# LIA.net
KiCad netlist of a schematic drawn in Altium Designer
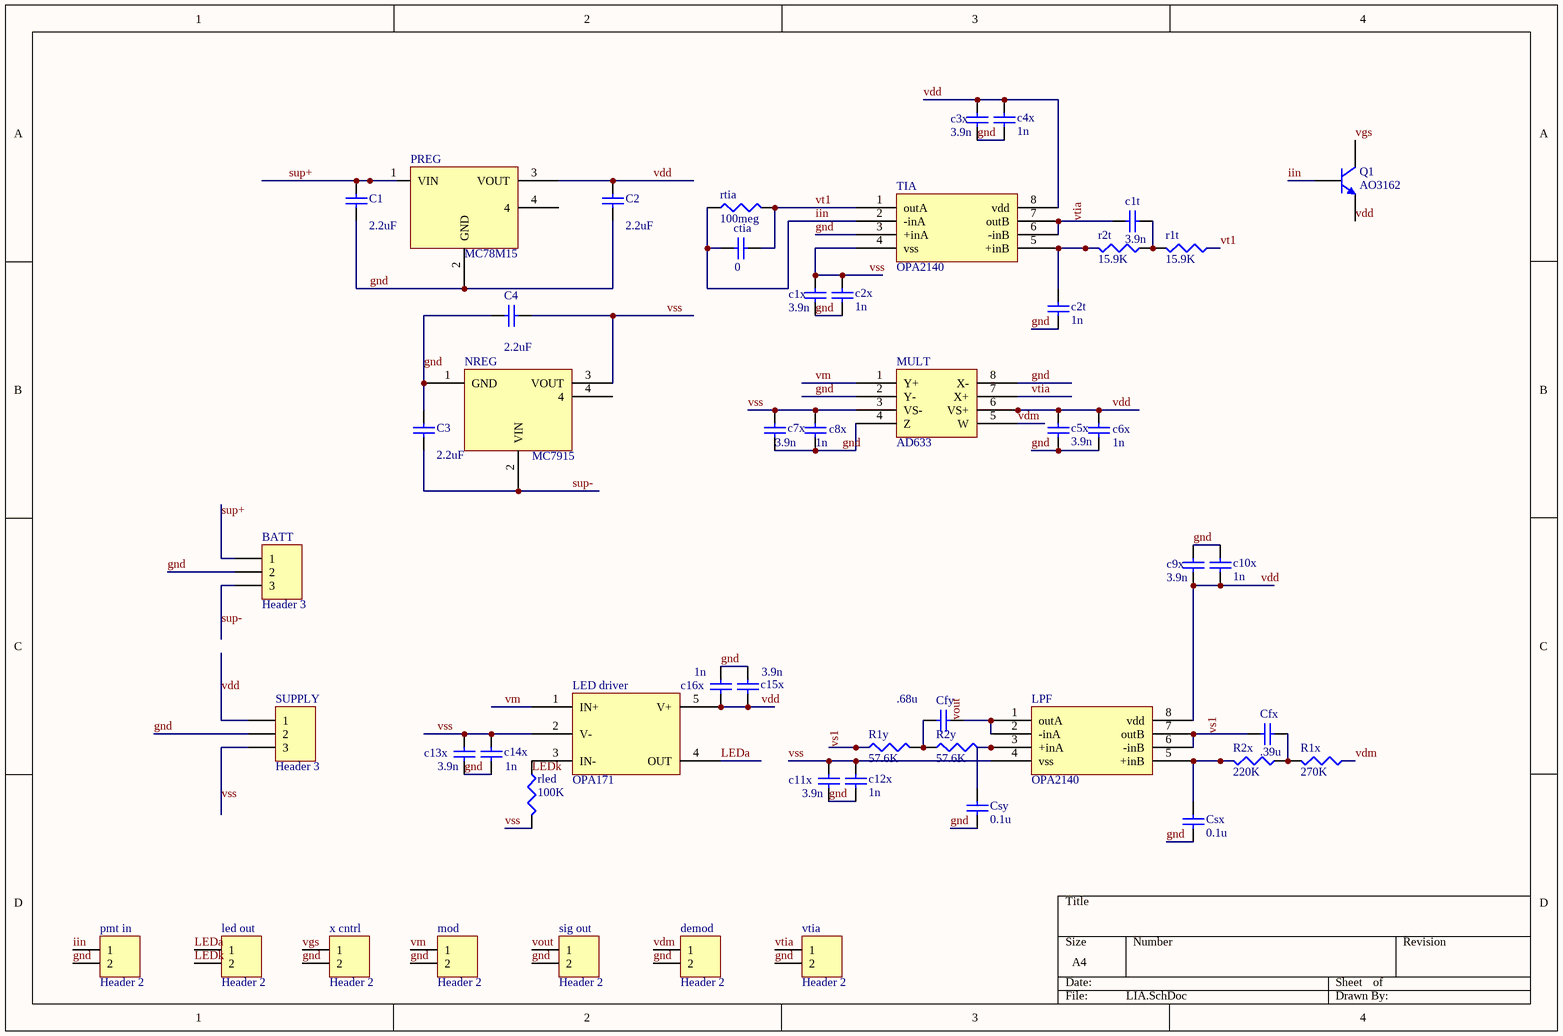
[diagram p0: LIA.SchDoc]

(export (version "E")
  (design (tool "Eeschema 10.0.6"))
  (components
    (comp (ref "BATT")
      (value "Header 3")
      (footprint "HDR1X3")
      (description "Header, 3-Pin")
      (fields (field (name "PUBLISHER") "Altium Limited"))
      (libsource (lib "Miscellaneous Connectors") (part "Header 3"))
    )
    (comp (ref "C1")
      (value "2.2uF")
      (footprint "0402")
      (description "Ceramic Chip Capacitor - Standard")
      (fields (field (name "Comment") "GRM155R61C225KE11D") (field (name "PUBLISHER") "Altium Limited"))
      (libsource (lib "KEMET Chip Capacitor") (part "C0402"))
    )
    (comp (ref "c1t")
      (value "3.9n")
      (footprint "0402")
      (description "Ceramic Chip Capacitor - Standard")
      (fields (field (name "Comment") "GRM155R71H392KA01D") (field (name "PUBLISHER") "Altium Limited"))
      (libsource (lib "KEMET Chip Capacitor") (part "C0402"))
    )
    (comp (ref "c1x")
      (value "3.9n")
      (footprint "0402")
      (description "Ceramic Chip Capacitor - Standard")
      (fields (field (name "Comment") "GRM155R71H392KA01D") (field (name "PUBLISHER") "Altium Limited"))
      (libsource (lib "KEMET Chip Capacitor") (part "C0402"))
    )
    (comp (ref "C2")
      (value "2.2uF")
      (footprint "0402")
      (description "Ceramic Chip Capacitor - Standard")
      (fields (field (name "Comment") "GRM155R61C225KE11D") (field (name "PUBLISHER") "Altium Limited"))
      (libsource (lib "KEMET Chip Capacitor") (part "C0402"))
    )
    (comp (ref "c2t")
      (value "1n")
      (footprint "0402")
      (description "Ceramic Chip Capacitor - Standard")
      (fields (field (name "Comment") "GRM155R71H102KA01D") (field (name "PUBLISHER") "Altium Limited"))
      (libsource (lib "KEMET Chip Capacitor") (part "C0402"))
    )
    (comp (ref "c2x")
      (value "1n")
      (footprint "0402")
      (description "Ceramic Chip Capacitor - Standard")
      (fields (field (name "Comment") "GRM155R71H102KA01D") (field (name "PUBLISHER") "Altium Limited"))
      (libsource (lib "KEMET Chip Capacitor") (part "C0402"))
    )
    (comp (ref "C3")
      (value "2.2uF")
      (footprint "0402")
      (description "Ceramic Chip Capacitor - Standard")
      (fields (field (name "Comment") "GRM155R61C225KE11D") (field (name "PUBLISHER") "Altium Limited"))
      (libsource (lib "KEMET Chip Capacitor") (part "C0402"))
    )
    (comp (ref "c3x")
      (value "3.9n")
      (footprint "0402")
      (description "Ceramic Chip Capacitor - Standard")
      (fields (field (name "Comment") "GRM155R71H392KA01D") (field (name "PUBLISHER") "Altium Limited"))
      (libsource (lib "KEMET Chip Capacitor") (part "C0402"))
    )
    (comp (ref "C4")
      (value "2.2uF")
      (footprint "0402")
      (description "Ceramic Chip Capacitor - Standard")
      (fields (field (name "Comment") "GRM155R61C225KE11D") (field (name "PUBLISHER") "Altium Limited"))
      (libsource (lib "KEMET Chip Capacitor") (part "C0402"))
    )
    (comp (ref "c4x")
      (value "1n")
      (footprint "0402")
      (description "Ceramic Chip Capacitor - Standard")
      (fields (field (name "Comment") "GRM155R71H102KA01D") (field (name "PUBLISHER") "Altium Limited"))
      (libsource (lib "KEMET Chip Capacitor") (part "C0402"))
    )
    (comp (ref "c5x")
      (value "3.9n")
      (footprint "0402")
      (description "Ceramic Chip Capacitor - Standard")
      (fields (field (name "Comment") "GRM155R71H392KA01D") (field (name "PUBLISHER") "Altium Limited"))
      (libsource (lib "KEMET Chip Capacitor") (part "C0402"))
    )
    (comp (ref "c6x")
      (value "1n")
      (footprint "0402")
      (description "Ceramic Chip Capacitor - Standard")
      (fields (field (name "Comment") "GRM155R71H102KA01D") (field (name "PUBLISHER") "Altium Limited"))
      (libsource (lib "KEMET Chip Capacitor") (part "C0402"))
    )
    (comp (ref "c7x")
      (value "3.9n")
      (footprint "0402")
      (description "Ceramic Chip Capacitor - Standard")
      (fields (field (name "Comment") "GRM155R71H392KA01D") (field (name "PUBLISHER") "Altium Limited"))
      (libsource (lib "KEMET Chip Capacitor") (part "C0402"))
    )
    (comp (ref "c8x")
      (value "1n")
      (footprint "0402")
      (description "Ceramic Chip Capacitor - Standard")
      (fields (field (name "Comment") "GRM155R71H102KA01D") (field (name "PUBLISHER") "Altium Limited"))
      (libsource (lib "KEMET Chip Capacitor") (part "C0402"))
    )
    (comp (ref "c9x")
      (value "3.9n")
      (footprint "0402")
      (description "Ceramic Chip Capacitor - Standard")
      (fields (field (name "Comment") "GRM155R71H392KA01D") (field (name "PUBLISHER") "Altium Limited"))
      (libsource (lib "KEMET Chip Capacitor") (part "C0402"))
    )
    (comp (ref "c10x")
      (value "1n")
      (footprint "0402")
      (description "Ceramic Chip Capacitor - Standard")
      (fields (field (name "Comment") "GRM155R71H102KA01D") (field (name "PUBLISHER") "Altium Limited"))
      (libsource (lib "KEMET Chip Capacitor") (part "C0402"))
    )
    (comp (ref "c11x")
      (value "3.9n")
      (footprint "0402")
      (description "Ceramic Chip Capacitor - Standard")
      (fields (field (name "Comment") "GRM155R71H392KA01D") (field (name "PUBLISHER") "Altium Limited"))
      (libsource (lib "KEMET Chip Capacitor") (part "C0402"))
    )
    (comp (ref "c12x")
      (value "1n")
      (footprint "0402")
      (description "Ceramic Chip Capacitor - Standard")
      (fields (field (name "Comment") "GRM155R71H102KA01D") (field (name "PUBLISHER") "Altium Limited"))
      (libsource (lib "KEMET Chip Capacitor") (part "C0402"))
    )
    (comp (ref "c13x")
      (value "3.9n")
      (footprint "0402")
      (description "Ceramic Chip Capacitor - Standard")
      (fields (field (name "Comment") "GRM155R71H392KA01D") (field (name "PUBLISHER") "Altium Limited"))
      (libsource (lib "KEMET Chip Capacitor") (part "C0402"))
    )
    (comp (ref "c14x")
      (value "1n")
      (footprint "0402")
      (description "Ceramic Chip Capacitor - Standard")
      (fields (field (name "Comment") "GRM155R71H102KA01D") (field (name "PUBLISHER") "Altium Limited"))
      (libsource (lib "KEMET Chip Capacitor") (part "C0402"))
    )
    (comp (ref "c15x")
      (value "3.9n")
      (footprint "0402")
      (description "Ceramic Chip Capacitor - Standard")
      (fields (field (name "Comment") "GRM155R71H392KA01D") (field (name "PUBLISHER") "Altium Limited"))
      (libsource (lib "KEMET Chip Capacitor") (part "C0402"))
    )
    (comp (ref "c16x")
      (value "1n")
      (footprint "0402")
      (description "Ceramic Chip Capacitor - Standard")
      (fields (field (name "Comment") "GRM155R71H102KA01D") (field (name "PUBLISHER") "Altium Limited"))
      (libsource (lib "KEMET Chip Capacitor") (part "C0402"))
    )
    (comp (ref "Cfx")
      (value ".39u")
      (footprint "0402")
      (description "Ceramic Chip Capacitor - Standard")
      (fields (field (name "Comment") "GRM155R61A394KE15D") (field (name "PUBLISHER") "Altium Limited"))
      (libsource (lib "KEMET Chip Capacitor") (part "C0402"))
    )
    (comp (ref "Cfy")
      (value ".68u")
      (footprint "0402")
      (description "Ceramic Chip Capacitor - Standard")
      (fields (field (name "Comment") "C1005X5R1C684K050BC") (field (name "PUBLISHER") "Altium Limited"))
      (libsource (lib "KEMET Chip Capacitor") (part "C0402"))
    )
    (comp (ref "Csx")
      (value "0.1u")
      (footprint "0402")
      (description "Ceramic Chip Capacitor - Standard")
      (fields (field (name "Comment") "GRM155R61C104KA88J") (field (name "PUBLISHER") "Altium Limited"))
      (libsource (lib "KEMET Chip Capacitor") (part "C0402"))
    )
    (comp (ref "Csy")
      (value "0.1u")
      (footprint "0402")
      (description "Ceramic Chip Capacitor - Standard")
      (fields (field (name "Comment") "GRM155R61C104KA88J") (field (name "PUBLISHER") "Altium Limited"))
      (libsource (lib "KEMET Chip Capacitor") (part "C0402"))
    )
    (comp (ref "ctia")
      (value "0")
      (footprint "1206")
      (description "Ceramic Chip Capacitor - Standard")
      (fields (field (name "PUBLISHER") "Altium Limited"))
      (libsource (lib "KEMET Chip Capacitor") (part "C1210"))
    )
    (comp (ref "demod")
      (value "Header 2")
      (footprint "HDR1X2")
      (description "Header, 2-Pin")
      (fields (field (name "PUBLISHER") "Altium Limited"))
      (libsource (lib "Miscellaneous Connectors") (part "Header 2"))
    )
    (comp (ref "LED driver")
      (value "OPA171")
      (footprint "S5")
      (description "Single supply opamp SOT 553")
      (libsource (lib "katschematic") (part "OPA171"))
    )
    (comp (ref "led out")
      (value "Header 2")
      (footprint "HDR1X2")
      (description "Header, 2-Pin")
      (fields (field (name "PUBLISHER") "Altium Limited"))
      (libsource (lib "Miscellaneous Connectors") (part "Header 2"))
    )
    (comp (ref "LPF")
      (value "OPA2140")
      (description "dual channel JFET op amp")
      (libsource (lib "Schlib1") (part "OPA2211"))
    )
    (comp (ref "mod")
      (value "Header 2")
      (footprint "HDR1X2")
      (description "Header, 2-Pin")
      (fields (field (name "PUBLISHER") "Altium Limited"))
      (libsource (lib "Miscellaneous Connectors") (part "Header 2"))
    )
    (comp (ref "MULT")
      (value "AD633")
      (footprint "D008_L")
      (description "Analog multiplier")
      (libsource (lib "katschematic") (part "AD633"))
    )
    (comp (ref "NREG")
      (value "MC7915")
      (footprint "D2PAK_L")
      (description "-15 V LDO regulator")
      (libsource (lib "katschematic") (part "MC7915"))
    )
    (comp (ref "pmt in")
      (value "Header 2")
      (footprint "HDR1X2")
      (description "Header, 2-Pin")
      (fields (field (name "PUBLISHER") "Altium Limited"))
      (libsource (lib "Miscellaneous Connectors") (part "Header 2"))
    )
    (comp (ref "PREG")
      (value "MC78M15")
      (footprint "D2PAK_L")
      (description "+15 V LDO regulator")
      (libsource (lib "katschematic") (part "MC78M15"))
    )
    (comp (ref "Q1")
      (value "AO3162")
      (footprint "SOT-23B_N")
      (description "NPN Bipolar Transistor")
      (fields (field (name "PUBLISHER") "Altium Limited"))
      (libsource (lib "Miscellaneous Devices") (part "QNPN"))
    )
    (comp (ref "r1t")
      (value "15.9K")
      (footprint "J1-0603")
      (description "Resistor")
      (fields (field (name "Comment") "RC0603JR-0716KL") (field (name "PUBLISHER") "Altium Limited"))
      (libsource (lib "Miscellaneous Devices") (part "Res3"))
    )
    (comp (ref "R1x")
      (value "270K")
      (footprint "J1-0603")
      (description "Resistor")
      (fields (field (name "Comment") "RC0603FR-07270KL") (field (name "PUBLISHER") "Altium Limited"))
      (libsource (lib "Miscellaneous Devices") (part "Res3"))
    )
    (comp (ref "R1y")
      (value "57.6K")
      (footprint "J1-0603")
      (description "Resistor")
      (fields (field (name "Comment") "RC0603FR-0757K6L") (field (name "PUBLISHER") "Altium Limited"))
      (libsource (lib "Miscellaneous Devices") (part "Res3"))
    )
    (comp (ref "r2t")
      (value "15.9K")
      (footprint "J1-0603")
      (description "Resistor")
      (fields (field (name "Comment") "RC0603JR-0716KL") (field (name "PUBLISHER") "Altium Limited"))
      (libsource (lib "Miscellaneous Devices") (part "Res3"))
    )
    (comp (ref "R2x")
      (value "220K")
      (footprint "J1-0603")
      (description "Resistor")
      (fields (field (name "Comment") "RC0603FR-07220KL") (field (name "PUBLISHER") "Altium Limited"))
      (libsource (lib "Miscellaneous Devices") (part "Res3"))
    )
    (comp (ref "R2y")
      (value "57.6K")
      (footprint "J1-0603")
      (description "Resistor")
      (fields (field (name "Comment") "RC0603FR-0757K6L") (field (name "PUBLISHER") "Altium Limited"))
      (libsource (lib "Miscellaneous Devices") (part "Res3"))
    )
    (comp (ref "rled")
      (value "100K")
      (footprint "J1-0603")
      (description "Resistor")
      (fields (field (name "Comment") "RC0603FR-07100KL") (field (name "PUBLISHER") "Altium Limited"))
      (libsource (lib "Miscellaneous Devices") (part "Res3"))
    )
    (comp (ref "rtia")
      (value "100meg")
      (footprint "1206")
      (description "Resistor")
      (fields (field (name "Comment") "HMC1206JT100M") (field (name "PUBLISHER") "Altium Limited"))
      (libsource (lib "Miscellaneous Devices") (part "Res3"))
    )
    (comp (ref "sig out")
      (value "Header 2")
      (footprint "HDR1X2")
      (description "Header, 2-Pin")
      (fields (field (name "PUBLISHER") "Altium Limited"))
      (libsource (lib "Miscellaneous Connectors") (part "Header 2"))
    )
    (comp (ref "SUPPLY")
      (value "Header 3")
      (footprint "HDR1X3")
      (description "Header, 3-Pin")
      (fields (field (name "PUBLISHER") "Altium Limited"))
      (libsource (lib "Miscellaneous Connectors") (part "Header 3"))
    )
    (comp (ref "TIA")
      (value "OPA2140")
      (description "dual channel JFET op amp")
      (libsource (lib "Schlib1") (part "OPA2211"))
    )
    (comp (ref "vtia")
      (value "Header 2")
      (footprint "HDR1X2")
      (description "Header, 2-Pin")
      (fields (field (name "PUBLISHER") "Altium Limited"))
      (libsource (lib "Miscellaneous Connectors") (part "Header 2"))
    )
    (comp (ref "x cntrl")
      (value "Header 2")
      (footprint "HDR1X2")
      (description "Header, 2-Pin")
      (fields (field (name "PUBLISHER") "Altium Limited"))
      (libsource (lib "Miscellaneous Connectors") (part "Header 2"))
    )
  )
  (nets
    (net (code "1") (name "/LEDa") (class "Default")
      (node (ref "LED driver") (pin "4") (pinfunction "OUT_4") (pintype "passive"))
      (node (ref "led out") (pin "1") (pinfunction "1_1") (pintype "passive"))
    )
    (net (code "2") (name "/LEDk") (class "Default")
      (node (ref "led out") (pin "2") (pinfunction "2_2") (pintype "passive"))
    )
    (net (code "3") (name "/gnd") (class "Default")
      (node (ref "BATT") (pin "2") (pinfunction "2_2") (pintype "passive"))
      (node (ref "C1") (pin "1") (pinfunction "1_1") (pintype "passive"))
      (node (ref "C2") (pin "1") (pinfunction "1_1") (pintype "passive"))
      (node (ref "C3") (pin "1") (pinfunction "1_1") (pintype "passive"))
      (node (ref "C4") (pin "1") (pinfunction "1_1") (pintype "passive"))
      (node (ref "Csx") (pin "1") (pinfunction "1_1") (pintype "passive"))
      (node (ref "Csy") (pin "1") (pinfunction "1_1") (pintype "passive"))
      (node (ref "MULT") (pin "2") (pinfunction "Y-_2") (pintype "passive"))
      (node (ref "MULT") (pin "4") (pinfunction "Z_4") (pintype "passive"))
      (node (ref "MULT") (pin "8") (pinfunction "X-_8") (pintype "passive"))
      (node (ref "NREG") (pin "1") (pinfunction "GND_1") (pintype "passive"))
      (node (ref "PREG") (pin "2") (pinfunction "GND_2") (pintype "passive"))
      (node (ref "SUPPLY") (pin "2") (pinfunction "2_2") (pintype "passive"))
      (node (ref "TIA") (pin "3") (pinfunction "+inA_3") (pintype "passive"))
      (node (ref "c10x") (pin "2") (pinfunction "2_2") (pintype "passive"))
      (node (ref "c11x") (pin "2") (pinfunction "2_2") (pintype "passive"))
      (node (ref "c12x") (pin "2") (pinfunction "2_2") (pintype "passive"))
      (node (ref "c13x") (pin "2") (pinfunction "2_2") (pintype "passive"))
      (node (ref "c14x") (pin "2") (pinfunction "2_2") (pintype "passive"))
      (node (ref "c15x") (pin "2") (pinfunction "2_2") (pintype "passive"))
      (node (ref "c16x") (pin "2") (pinfunction "2_2") (pintype "passive"))
      (node (ref "c1x") (pin "2") (pinfunction "2_2") (pintype "passive"))
      (node (ref "c2t") (pin "1") (pinfunction "1_1") (pintype "passive"))
      (node (ref "c2x") (pin "2") (pinfunction "2_2") (pintype "passive"))
      (node (ref "c3x") (pin "2") (pinfunction "2_2") (pintype "passive"))
      (node (ref "c4x") (pin "2") (pinfunction "2_2") (pintype "passive"))
      (node (ref "c5x") (pin "1") (pinfunction "1_1") (pintype "passive"))
      (node (ref "c6x") (pin "1") (pinfunction "1_1") (pintype "passive"))
      (node (ref "c7x") (pin "1") (pinfunction "1_1") (pintype "passive"))
      (node (ref "c8x") (pin "1") (pinfunction "1_1") (pintype "passive"))
      (node (ref "c9x") (pin "2") (pinfunction "2_2") (pintype "passive"))
      (node (ref "demod") (pin "2") (pinfunction "2_2") (pintype "passive"))
      (node (ref "mod") (pin "2") (pinfunction "2_2") (pintype "passive"))
      (node (ref "pmt in") (pin "2") (pinfunction "2_2") (pintype "passive"))
      (node (ref "sig out") (pin "2") (pinfunction "2_2") (pintype "passive"))
      (node (ref "vtia") (pin "2") (pinfunction "2_2") (pintype "passive"))
      (node (ref "x cntrl") (pin "2") (pinfunction "2_2") (pintype "passive"))
    )
    (net (code "4") (name "/iin") (class "Default")
      (node (ref "Q1") (pin "2") (pinfunction "B_2") (pintype "passive"))
      (node (ref "TIA") (pin "2") (pinfunction "-inA_2") (pintype "passive"))
      (node (ref "ctia") (pin "1") (pinfunction "1_1") (pintype "passive"))
      (node (ref "pmt in") (pin "1") (pinfunction "1_1") (pintype "passive"))
      (node (ref "rtia") (pin "1") (pinfunction "1_1") (pintype "passive"))
    )
    (net (code "5") (name "/sup+") (class "Default")
      (node (ref "BATT") (pin "1") (pinfunction "1_1") (pintype "passive"))
      (node (ref "C1") (pin "2") (pinfunction "2_2") (pintype "passive"))
      (node (ref "PREG") (pin "1") (pinfunction "VIN_1") (pintype "passive"))
    )
    (net (code "6") (name "/sup-") (class "Default")
      (node (ref "BATT") (pin "3") (pinfunction "3_3") (pintype "passive"))
      (node (ref "C3") (pin "2") (pinfunction "2_2") (pintype "passive"))
      (node (ref "NREG") (pin "2") (pinfunction "VIN_2") (pintype "passive"))
    )
    (net (code "7") (name "/vdd") (class "Default")
      (node (ref "C2") (pin "2") (pinfunction "2_2") (pintype "passive"))
      (node (ref "LED driver") (pin "5") (pinfunction "V+_5") (pintype "passive"))
      (node (ref "LPF") (pin "8") (pinfunction "vdd_8") (pintype "passive"))
      (node (ref "MULT") (pin "6") (pinfunction "VS+_6") (pintype "passive"))
      (node (ref "PREG") (pin "3") (pinfunction "VOUT_3") (pintype "passive"))
      (node (ref "Q1") (pin "3") (pinfunction "E_3") (pintype "passive"))
      (node (ref "SUPPLY") (pin "1") (pinfunction "1_1") (pintype "passive"))
      (node (ref "TIA") (pin "8") (pinfunction "vdd_8") (pintype "passive"))
      (node (ref "c10x") (pin "1") (pinfunction "1_1") (pintype "passive"))
      (node (ref "c15x") (pin "1") (pinfunction "1_1") (pintype "passive"))
      (node (ref "c16x") (pin "1") (pinfunction "1_1") (pintype "passive"))
      (node (ref "c3x") (pin "1") (pinfunction "1_1") (pintype "passive"))
      (node (ref "c4x") (pin "1") (pinfunction "1_1") (pintype "passive"))
      (node (ref "c5x") (pin "2") (pinfunction "2_2") (pintype "passive"))
      (node (ref "c6x") (pin "2") (pinfunction "2_2") (pintype "passive"))
      (node (ref "c9x") (pin "1") (pinfunction "1_1") (pintype "passive"))
    )
    (net (code "8") (name "/vdm") (class "Default")
      (node (ref "MULT") (pin "5") (pinfunction "W_5") (pintype "passive"))
      (node (ref "R1x") (pin "1") (pinfunction "1_1") (pintype "passive"))
      (node (ref "demod") (pin "1") (pinfunction "1_1") (pintype "passive"))
    )
    (net (code "9") (name "/vgs") (class "Default")
      (node (ref "Q1") (pin "1") (pinfunction "C_1") (pintype "passive"))
      (node (ref "x cntrl") (pin "1") (pinfunction "1_1") (pintype "passive"))
    )
    (net (code "10") (name "/vm") (class "Default")
      (node (ref "LED driver") (pin "1") (pinfunction "IN+_1") (pintype "passive"))
      (node (ref "MULT") (pin "1") (pinfunction "Y+_1") (pintype "passive"))
      (node (ref "mod") (pin "1") (pinfunction "1_1") (pintype "passive"))
    )
    (net (code "11") (name "/vout") (class "Default")
      (node (ref "Cfy") (pin "1") (pinfunction "1_1") (pintype "passive"))
      (node (ref "LPF") (pin "1") (pinfunction "outA_1") (pintype "passive"))
      (node (ref "LPF") (pin "2") (pinfunction "-inA_2") (pintype "passive"))
      (node (ref "sig out") (pin "1") (pinfunction "1_1") (pintype "passive"))
    )
    (net (code "12") (name "/vs1") (class "Default")
      (node (ref "Cfx") (pin "2") (pinfunction "2_2") (pintype "passive"))
      (node (ref "LPF") (pin "6") (pinfunction "-inB_6") (pintype "passive"))
      (node (ref "LPF") (pin "7") (pinfunction "outB_7") (pintype "passive"))
      (node (ref "R1y") (pin "1") (pinfunction "1_1") (pintype "passive"))
    )
    (net (code "13") (name "/vss") (class "Default")
      (node (ref "C4") (pin "2") (pinfunction "2_2") (pintype "passive"))
      (node (ref "LED driver") (pin "2") (pinfunction "V-_2") (pintype "passive"))
      (node (ref "LPF") (pin "4") (pinfunction "vss_4") (pintype "passive"))
      (node (ref "MULT") (pin "3") (pinfunction "VS-_3") (pintype "passive"))
      (node (ref "NREG") (pin "3") (pinfunction "VOUT_3") (pintype "passive"))
      (node (ref "SUPPLY") (pin "3") (pinfunction "3_3") (pintype "passive"))
      (node (ref "TIA") (pin "4") (pinfunction "vss_4") (pintype "passive"))
      (node (ref "c11x") (pin "1") (pinfunction "1_1") (pintype "passive"))
      (node (ref "c12x") (pin "1") (pinfunction "1_1") (pintype "passive"))
      (node (ref "c13x") (pin "1") (pinfunction "1_1") (pintype "passive"))
      (node (ref "c14x") (pin "1") (pinfunction "1_1") (pintype "passive"))
      (node (ref "c1x") (pin "1") (pinfunction "1_1") (pintype "passive"))
      (node (ref "c2x") (pin "1") (pinfunction "1_1") (pintype "passive"))
      (node (ref "c7x") (pin "2") (pinfunction "2_2") (pintype "passive"))
      (node (ref "c8x") (pin "2") (pinfunction "2_2") (pintype "passive"))
      (node (ref "rled") (pin "2") (pinfunction "2_2") (pintype "passive"))
    )
    (net (code "14") (name "/vt1") (class "Default")
      (node (ref "TIA") (pin "1") (pinfunction "outA_1") (pintype "passive"))
      (node (ref "ctia") (pin "2") (pinfunction "2_2") (pintype "passive"))
      (node (ref "r1t") (pin "1") (pinfunction "1_1") (pintype "passive"))
      (node (ref "rtia") (pin "2") (pinfunction "2_2") (pintype "passive"))
    )
    (net (code "15") (name "/vtia") (class "Default")
      (node (ref "MULT") (pin "7") (pinfunction "X+_7") (pintype "passive"))
      (node (ref "TIA") (pin "6") (pinfunction "-inB_6") (pintype "passive"))
      (node (ref "TIA") (pin "7") (pinfunction "outB_7") (pintype "passive"))
      (node (ref "c1t") (pin "2") (pinfunction "2_2") (pintype "passive"))
      (node (ref "vtia") (pin "1") (pinfunction "1_1") (pintype "passive"))
    )
    (net (code "16") (name "Net-(Cfx-Pad1)") (class "Default")
      (node (ref "Cfx") (pin "1") (pinfunction "1_1") (pintype "passive"))
      (node (ref "R1x") (pin "2") (pinfunction "2_2") (pintype "passive"))
      (node (ref "R2x") (pin "1") (pinfunction "1_1") (pintype "passive"))
    )
    (net (code "17") (name "Net-(Cfy-Pad2)") (class "Default")
      (node (ref "Cfy") (pin "2") (pinfunction "2_2") (pintype "passive"))
      (node (ref "R1y") (pin "2") (pinfunction "2_2") (pintype "passive"))
      (node (ref "R2y") (pin "1") (pinfunction "1_1") (pintype "passive"))
    )
    (net (code "18") (name "Net-(LED driver-IN-)") (class "Default")
      (node (ref "LED driver") (pin "3") (pinfunction "IN-_3") (pintype "passive"))
      (node (ref "rled") (pin "1") (pinfunction "1_1") (pintype "passive"))
    )
    (net (code "19") (name "Net-(LPF-+inA)") (class "Default")
      (node (ref "Csy") (pin "2") (pinfunction "2_2") (pintype "passive"))
      (node (ref "LPF") (pin "3") (pinfunction "+inA_3") (pintype "passive"))
      (node (ref "R2y") (pin "2") (pinfunction "2_2") (pintype "passive"))
    )
    (net (code "20") (name "Net-(LPF-+inB)") (class "Default")
      (node (ref "Csx") (pin "2") (pinfunction "2_2") (pintype "passive"))
      (node (ref "LPF") (pin "5") (pinfunction "+inB_5") (pintype "passive"))
      (node (ref "R2x") (pin "2") (pinfunction "2_2") (pintype "passive"))
    )
    (net (code "21") (name "Net-(TIA-+inB)") (class "Default")
      (node (ref "TIA") (pin "5") (pinfunction "+inB_5") (pintype "passive"))
      (node (ref "c2t") (pin "2") (pinfunction "2_2") (pintype "passive"))
      (node (ref "r2t") (pin "2") (pinfunction "2_2") (pintype "passive"))
    )
    (net (code "22") (name "Net-(c1t-Pad1)") (class "Default")
      (node (ref "c1t") (pin "1") (pinfunction "1_1") (pintype "passive"))
      (node (ref "r1t") (pin "2") (pinfunction "2_2") (pintype "passive"))
      (node (ref "r2t") (pin "1") (pinfunction "1_1") (pintype "passive"))
    )
    (net (code "23") (name "unconnected-(NREG-Pad4)") (class "Default")
      (node (ref "NREG") (pin "4") (pinfunction "4_4") (pintype "passive"))
    )
    (net (code "24") (name "unconnected-(PREG-Pad4)") (class "Default")
      (node (ref "PREG") (pin "4") (pinfunction "4_4") (pintype "passive"))
    )
  )
)
